# NEW_PDB.net
KiCad netlist of a schematic drawn in Altium Designer
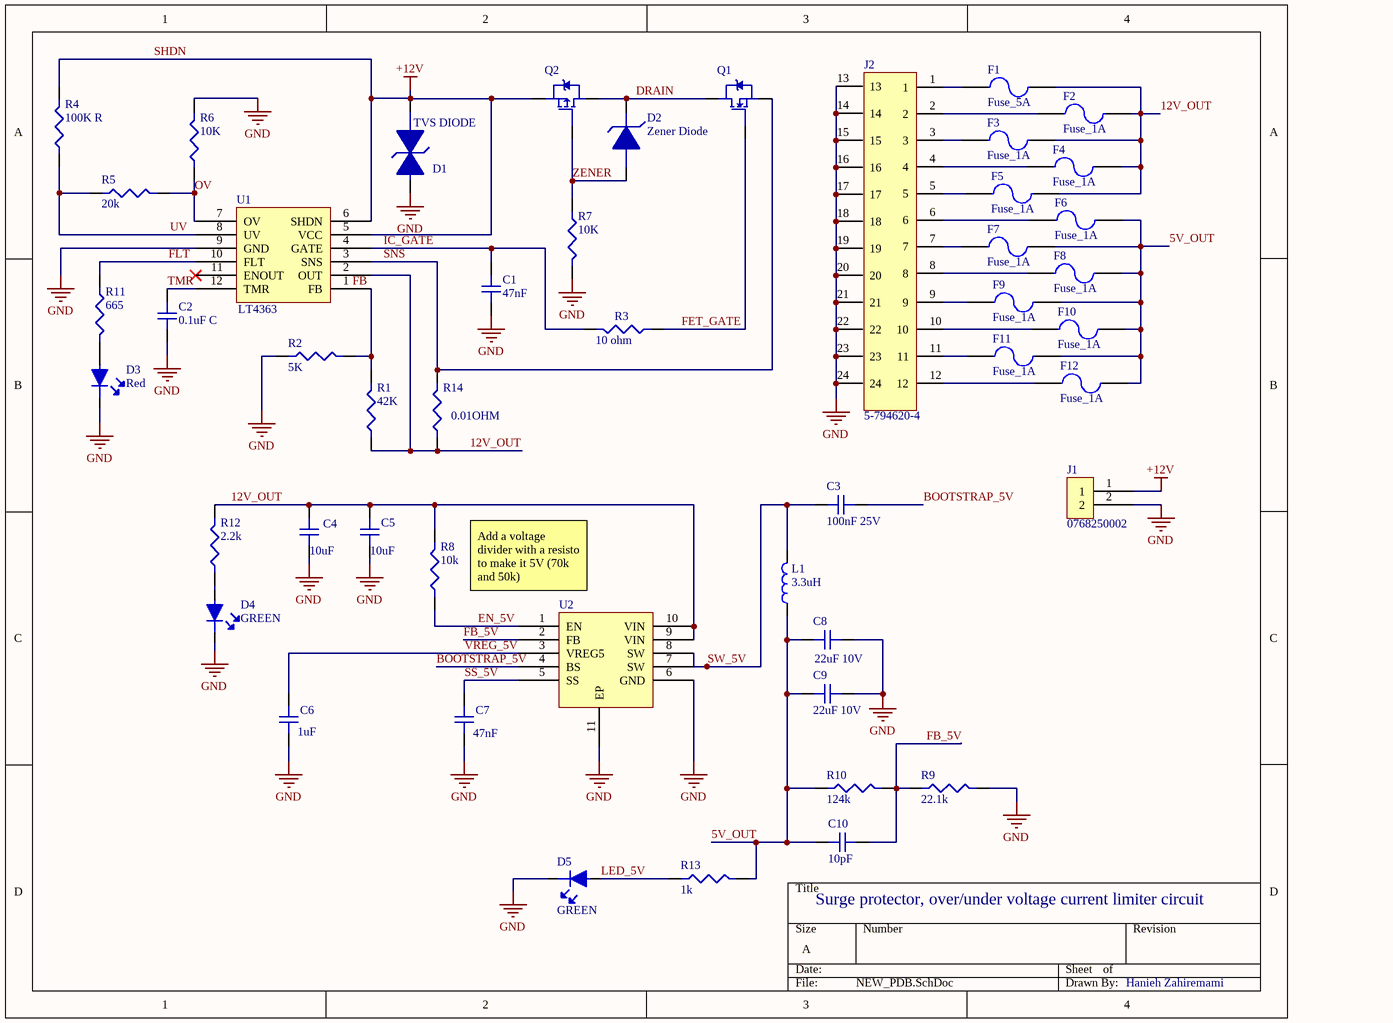
[diagram p0: NEW_PDB.SchDoc]

(export (version "E")
  (design (tool "Eeschema 10.0.6"))
  (components
    (comp (ref "C1")
      (value "47nF")
      (footprint "CAPC1613X09N")
      (description "CAP CER 0.047UF 50V X7R 0603")
      (fields
        (field (name "MANUFACTURER") "Murata")
        (field (name "MANUFACTURER PART NUMBER") "GCM188R71H473KA55D")
      )
      (libsource (lib "PDB_components") (part "GCM188R71H473KA55D"))
    )
    (comp (ref "C2")
      (value "0.1uF C")
      (footprint "CAPC1613X09N")
      (description "Cap Ceramic 0.1uF 25V X5R 10% SMD 0402 85C Paper T/R")
      (fields
        (field (name "MANUFACTURER") "Samsung")
        (field (name "MANUFACTURER PART NUMBER") "CL05A104KA5NNNC")
      )
      (libsource (lib "PDB_components") (part "CL05A104KA5NNNC"))
    )
    (comp (ref "C3")
      (value "100nF 25V")
      (footprint "CAPC1613X09N")
      (description "CAP CER 0.047UF 50V X7R 0603")
      (fields
        (field (name "MANUFACTURER") "Murata")
        (field (name "MANUFACTURER PART NUMBER") "GCM188R71H473KA55D")
      )
      (libsource (lib "PDB_components") (part "GCM188R71H473KA55D"))
    )
    (comp (ref "C4")
      (value "10uF")
      (footprint "CAPC1613X09N")
      (description "CAP CER 0.047UF 50V X7R 0603")
      (fields
        (field (name "MANUFACTURER") "Murata")
        (field (name "MANUFACTURER PART NUMBER") "GCM188R71H473KA55D")
      )
      (libsource (lib "PDB_components") (part "GCM188R71H473KA55D"))
    )
    (comp (ref "C5")
      (value "10uF")
      (footprint "CAPC1613X09N")
      (description "CAP CER 0.047UF 50V X7R 0603")
      (fields
        (field (name "MANUFACTURER") "Murata")
        (field (name "MANUFACTURER PART NUMBER") "GCM188R71H473KA55D")
      )
      (libsource (lib "PDB_components") (part "GCM188R71H473KA55D"))
    )
    (comp (ref "C6")
      (value "1uF")
      (footprint "CAPC1613X09N")
      (description "CAP CER 0.047UF 50V X7R 0603")
      (fields
        (field (name "MANUFACTURER") "Murata")
        (field (name "MANUFACTURER PART NUMBER") "GCM188R71H473KA55D")
      )
      (libsource (lib "PDB_components") (part "GCM188R71H473KA55D"))
    )
    (comp (ref "C7")
      (value "47nF")
      (footprint "CAPC1613X09N")
      (description "CAP CER 0.047UF 50V X7R 0603")
      (fields
        (field (name "MANUFACTURER") "Murata")
        (field (name "MANUFACTURER PART NUMBER") "GCM188R71H473KA55D")
      )
      (libsource (lib "PDB_components") (part "GCM188R71H473KA55D"))
    )
    (comp (ref "C8")
      (value "22uF 10V")
      (footprint "CAPC1613X09N")
      (description "CAP CER 0.047UF 50V X7R 0603")
      (fields
        (field (name "MANUFACTURER") "Murata")
        (field (name "MANUFACTURER PART NUMBER") "GCM188R71H473KA55D")
      )
      (libsource (lib "PDB_components") (part "GCM188R71H473KA55D"))
    )
    (comp (ref "C9")
      (value "22uF 10V")
      (footprint "CAPC1613X09N")
      (description "CAP CER 0.047UF 50V X7R 0603")
      (fields
        (field (name "MANUFACTURER") "Murata")
        (field (name "MANUFACTURER PART NUMBER") "GCM188R71H473KA55D")
      )
      (libsource (lib "PDB_components") (part "GCM188R71H473KA55D"))
    )
    (comp (ref "C10")
      (value "10pF")
      (footprint "CAPC1613X09N")
      (description "CAP CER 0.047UF 50V X7R 0603")
      (fields
        (field (name "MANUFACTURER") "Murata")
        (field (name "MANUFACTURER PART NUMBER") "GCM188R71H473KA55D")
      )
      (libsource (lib "PDB_components") (part "GCM188R71H473KA55D"))
    )
    (comp (ref "D1")
      (value "TVS DIODE")
      (footprint "DIODE_TVS")
      (description "TVS DIODE 58VWM 93.6VC SMA")
      (fields (field (name "MANUFACTURER") "Diodes") (field (name "MANUFACTURER PART NUMBER") "SMAJ58A-13-F"))
      (libsource (lib "PDB_components") (part "SMAJ58A-13-F"))
    )
    (comp (ref "D2")
      (value "Zener Diode")
      (footprint "DIOM3716X14N")
      (description "DIODE GEN PURP 100V 150MA SOD123")
      (fields (field (name "MANUFACTURER") "MCC") (field (name "MANUFACTURER PART NUMBER") "1N4148W-TP"))
      (libsource (lib "PDB_components") (part "1N4148W-TP"))
    )
    (comp (ref "D3")
      (value "Red")
      (footprint "LED2")
      (description "LED RED CLEAR 0603 SMD")
      (fields
        (field (name "MANUFACTURER") "Wurth Electronics")
        (field (name "MANUFACTURER PART NUMBER") "150060VS75000")
      )
      (libsource (lib "PDB_components") (part "150060VS75000"))
    )
    (comp (ref "D4")
      (value "GREEN")
      (footprint "LED2")
      (description "LED GREEN CLEAR 0603 SMD")
      (fields
        (field (name "MANUFACTURER") "Wurth Electronics")
        (field (name "MANUFACTURER PART NUMBER") "150060VS75000")
      )
      (libsource (lib "PDB_components") (part "150060VS75000"))
    )
    (comp (ref "D5")
      (value "GREEN")
      (footprint "LED2")
      (description "LED GREEN CLEAR 0603 SMD")
      (fields
        (field (name "MANUFACTURER") "Wurth Electronics")
        (field (name "MANUFACTURER PART NUMBER") "150060VS75000")
      )
      (libsource (lib "PDB_components") (part "150060VS75000"))
    )
    (comp (ref "F1")
      (value "Fuse_5A")
      (footprint "PDB_Components:FUSE")
      (description "0466005.NR FUSE BOARD MNT 5A 32VAC/VDC 1206")
      (fields (field (name "PUBLISHER") "Altium Limited"))
      (libsource (lib "Miscellaneous Devices") (part "Fuse 2"))
    )
    (comp (ref "F2")
      (value "Fuse_1A")
      (footprint "FUSE")
      (description "0466001.NR FUSE BOARD MNT 1A 63VAC/VDC 1206")
      (fields (field (name "PUBLISHER") "Altium Limited"))
      (libsource (lib "Miscellaneous Devices") (part "Fuse 2"))
    )
    (comp (ref "F3")
      (value "Fuse_1A")
      (footprint "FUSE")
      (description "0466001.NR FUSE BOARD MNT 1A 63VAC/VDC 1206")
      (fields (field (name "PUBLISHER") "Altium Limited"))
      (libsource (lib "Miscellaneous Devices") (part "Fuse 2"))
    )
    (comp (ref "F4")
      (value "Fuse_1A")
      (footprint "FUSE")
      (description "0466001.NR FUSE BOARD MNT 1A 63VAC/VDC 1206")
      (fields (field (name "PUBLISHER") "Altium Limited"))
      (libsource (lib "Miscellaneous Devices") (part "Fuse 2"))
    )
    (comp (ref "F5")
      (value "Fuse_1A")
      (footprint "FUSE")
      (description "0466001.NR FUSE BOARD MNT 1A 63VAC/VDC 1206")
      (fields (field (name "PUBLISHER") "Altium Limited"))
      (libsource (lib "Miscellaneous Devices") (part "Fuse 2"))
    )
    (comp (ref "F6")
      (value "Fuse_1A")
      (footprint "FUSE")
      (description "0466001.NR FUSE BOARD MNT 1A 63VAC/VDC 1206")
      (fields (field (name "PUBLISHER") "Altium Limited"))
      (libsource (lib "Miscellaneous Devices") (part "Fuse 2"))
    )
    (comp (ref "F7")
      (value "Fuse_1A")
      (footprint "FUSE")
      (description "0466001.NR FUSE BOARD MNT 1A 63VAC/VDC 1206")
      (fields (field (name "PUBLISHER") "Altium Limited"))
      (libsource (lib "Miscellaneous Devices") (part "Fuse 2"))
    )
    (comp (ref "F8")
      (value "Fuse_1A")
      (footprint "FUSE")
      (description "0466001.NR FUSE BOARD MNT 1A 63VAC/VDC 1206")
      (fields (field (name "PUBLISHER") "Altium Limited"))
      (libsource (lib "Miscellaneous Devices") (part "Fuse 2"))
    )
    (comp (ref "F9")
      (value "Fuse_1A")
      (footprint "FUSE")
      (description "0466001.NR FUSE BOARD MNT 1A 63VAC/VDC 1206")
      (fields (field (name "PUBLISHER") "Altium Limited"))
      (libsource (lib "Miscellaneous Devices") (part "Fuse 2"))
    )
    (comp (ref "F10")
      (value "Fuse_1A")
      (footprint "FUSE")
      (description "0466001.NR FUSE BOARD MNT 1A 63VAC/VDC 1206")
      (fields (field (name "PUBLISHER") "Altium Limited"))
      (libsource (lib "Miscellaneous Devices") (part "Fuse 2"))
    )
    (comp (ref "F11")
      (value "Fuse_1A")
      (footprint "FUSE")
      (description "0466001.NR FUSE BOARD MNT 1A 63VAC/VDC 1206")
      (fields (field (name "PUBLISHER") "Altium Limited"))
      (libsource (lib "Miscellaneous Devices") (part "Fuse 2"))
    )
    (comp (ref "F12")
      (value "Fuse_1A")
      (footprint "FUSE")
      (description "0466001.NR FUSE BOARD MNT 1A 63VAC/VDC 1206")
      (fields (field (name "PUBLISHER") "Altium Limited"))
      (libsource (lib "Miscellaneous Devices") (part "Fuse 2"))
    )
    (comp (ref "J1")
      (value "0768250002")
      (footprint "MOLEX_2PIN_MEGAFIT")
      (description "CONN_2Position_MEGAFIT Molex Through Hole, Right Angle Tin")
      (fields (field (name "MANUFACTURER") "Molex"))
      (libsource (lib "PDB_components") (part "0768250002"))
    )
    (comp (ref "J2")
      (value "5-794620-4")
      (footprint "PDB_OUT")
      (description "CONN HEADER R/A 24POS 3MM")
      (libsource (lib "PDB_components") (part "5-794620-4"))
    )
    (comp (ref "L1")
      (value "3.3uH")
      (footprint "IND-6mm")
      (description "IND 3.3µH 6.5A 25.2 mOhm Max Nonstandard")
      (fields
        (field (name "MANUFACTURER") "Murata")
        (field (name "MANUFACTURER PART NUMBER") "1264EY-3R3N=P3")
      )
      (libsource (lib "PDB_components") (part "1264EY-3R3N=P3"))
    )
    (comp (ref "Q1")
      (value "IRLR2908TRLPBF")
      (footprint "DPAK")
      (description "MOSFET N-CH 80V 30A DPAK")
      (fields (field (name "MANUFACTURER") "International Rectifier"))
      (libsource (lib "PDB_components") (part "IRLR2908TRLPBF"))
    )
    (comp (ref "Q2")
      (value "STD35P6LLF6")
      (footprint "DPAK")
      (description "POWER MOSFET")
      (fields (field (name "MANUFACTURER") "STMicroelectronics"))
      (libsource (lib "PDB_components") (part "STD35P6LLF6"))
    )
    (comp (ref "R1")
      (value "42K")
      (footprint "R0805")
      (description "Res Thin Film 0805 100K Ohm 0.1% 0.125W(1/8W) ±25ppm/C Molded SMD Automotive Punched T/R")
      (fields
        (field (name "MANUFACTURER") "Panasonic")
        (field (name "MANUFACTURER PART NUMBER") "ERA-6AEB104V")
      )
      (libsource (lib "") (part "ERA-6AEB104V_1"))
    )
    (comp (ref "R2")
      (value "5K")
      (footprint "PDB_Components:R0805")
      (description "Thin Film Resistors - SMD 200mW 5Kohm 0.1% 25ppm")
      (fields
        (field (name "MANUFACTURER") "Vishay Dale Thin Film")
        (field (name "MANUFACTURER PART NUMBER") "PNM0805E5001BST5")
      )
      (libsource (lib "PDB_components") (part "PNM0805E5001BST5_1"))
    )
    (comp (ref "R3")
      (value "10 ohm")
      (footprint "R0805")
      (description "RES SMD 10 OHM 1% 1/3W 0805")
      (fields
        (field (name "MANUFACTURER") "Susumu")
        (field (name "MANUFACTURER PART NUMBER") "RL1220S-100-F")
      )
      (libsource (lib "PDB_components") (part "RL1220S-100-F"))
    )
    (comp (ref "R4")
      (value "100K R")
      (footprint "R0805")
      (description "RES 220K OHM 1/8W 1% 0805 SMD")
      (fields (field (name "MANUFACTURER") "Rohm") (field (name "MANUFACTURER PART NUMBER") "KTR10EZPF2203"))
      (libsource (lib "PDB_components") (part "KTR10EZPF2203"))
    )
    (comp (ref "R5")
      (value "20k")
      (footprint "R0805")
      (description "Res Thin Film 0805 10K Ohm 0.5% 0.1W(1/10W) ±25ppm/C Molded SMD Paper T/R")
      (fields
        (field (name "MANUFACTURER") "Stackpole Electronics")
        (field (name "MANUFACTURER PART NUMBER") "RNCF0805DTE10K0")
      )
      (libsource (lib "PDB_components") (part "RNCF0805DTE10K0"))
    )
    (comp (ref "R6")
      (value "10K")
      (footprint "R0805")
      (description "Res Thin Film 0805 10K Ohm 0.5% 0.1W(1/10W) ±25ppm/C Molded SMD Paper T/R")
      (fields
        (field (name "MANUFACTURER") "Stackpole Electronics")
        (field (name "MANUFACTURER PART NUMBER") "RNCF0805DTE10K0")
      )
      (libsource (lib "PDB_components") (part "RNCF0805DTE10K0"))
    )
    (comp (ref "R7")
      (value "10K")
      (footprint "R0805")
      (description "Res Thin Film 0805 10K Ohm 0.5% 0.1W(1/10W) ±25ppm/C Molded SMD Paper T/R")
      (fields
        (field (name "MANUFACTURER") "Stackpole Electronics")
        (field (name "MANUFACTURER PART NUMBER") "RNCF0805DTE10K0")
      )
      (libsource (lib "PDB_components") (part "RNCF0805DTE10K0"))
    )
    (comp (ref "R8")
      (value "10k")
      (footprint "R0805")
      (description "Res Thin Film 0805 1K Ohm 0.1% 0.125W(1/8W) ±25ppm/C Molded SMD Automotive Punched T/R")
      (fields
        (field (name "MANUFACTURER") "Panasonic")
        (field (name "MANUFACTURER PART NUMBER") "ERA-6AEB104V")
      )
      (libsource (lib "") (part "ERA-6AEB104V_1"))
    )
    (comp (ref "R9")
      (value "22.1k")
      (footprint "R0805")
      (description "Res Thin Film 0805 22.1K Ohm 0.1% 0.125W(1/8W) ±25ppm/C Molded SMD Automotive Punched T/R")
      (fields
        (field (name "MANUFACTURER") "Panasonic")
        (field (name "MANUFACTURER PART NUMBER") "ERA-6AEB104V")
      )
      (libsource (lib "PDB_components") (part "ERA-6AEB104V"))
    )
    (comp (ref "R10")
      (value "124k")
      (footprint "R0805")
      (description "Res Thin Film 0805 124K Ohm 0.1% 0.125W(1/8W) ±25ppm/C Molded SMD Automotive Punched T/R")
      (fields
        (field (name "MANUFACTURER") "Panasonic")
        (field (name "MANUFACTURER PART NUMBER") "ERA-6AEB104V")
      )
      (libsource (lib "PDB_components") (part "ERA-6AEB104V"))
    )
    (comp (ref "R11")
      (value "665")
      (footprint "R0805")
      (description "Res Thin Film 0805 22.1K Ohm 0.1% 0.125W(1/8W) ±25ppm/C Molded SMD Automotive Punched T/R")
      (fields
        (field (name "MANUFACTURER") "Panasonic")
        (field (name "MANUFACTURER PART NUMBER") "ERA-6AEB104V")
      )
      (libsource (lib "PDB_components") (part "ERA-6AEB104V"))
    )
    (comp (ref "R12")
      (value "2.2k")
      (footprint "R0805")
      (description "Res Thin Film 0805 22.1K Ohm 0.1% 0.125W(1/8W) ±25ppm/C Molded SMD Automotive Punched T/R")
      (fields
        (field (name "MANUFACTURER") "Panasonic")
        (field (name "MANUFACTURER PART NUMBER") "ERA-6AEB104V")
      )
      (libsource (lib "PDB_components") (part "ERA-6AEB104V"))
    )
    (comp (ref "R13")
      (value "1k")
      (footprint "R0805")
      (description "Res Thin Film 0805 22.1K Ohm 0.1% 0.125W(1/8W) ±25ppm/C Molded SMD Automotive Punched T/R")
      (fields
        (field (name "MANUFACTURER") "Panasonic")
        (field (name "MANUFACTURER PART NUMBER") "ERA-6AEB104V")
      )
      (libsource (lib "PDB_components") (part "ERA-6AEB104V"))
    )
    (comp (ref "R14")
      (value "0.01OHM")
      (footprint "R2512")
      (description "RES SMD 0.01 OHM 1% 2W 2512")
      (fields
        (field (name "MANUFACTURER") "Yageo")
        (field (name "MANUFACTURER PART NUMBER") "PE2512FKE7W0R01L")
      )
      (libsource (lib "PDB_components") (part "PE2512FKE7W0R01L"))
    )
    (comp (ref "U1")
      (value "LT4363")
      (footprint "TSOP65P490X110-12N")
      (description "IC SURGE STOPPER HV 12-MSOP")
      (fields
        (field (name "MANUFACTURER") "Analog Devices / Linear Technology")
        (field (name "MANUFACTURER PART NUMBER") "LT4363CMS-2#PBF")
      )
      (libsource (lib "PDB_components") (part "LT4363CMS-2#PBF"))
    )
    (comp (ref "U2")
      (value "AP65550FN-7")
      (footprint "DFN-10")
      (description "IC BUCK SYNC 5A, 18V VIN MAX 650kHz COT Step-Down Conv")
      (fields (field (name "MANUFACTURER") "Diodes"))
      (libsource (lib "PDB_components") (part "AP65550FN-7"))
    )
  )
  (nets
    (net (code "1") (name "+12V") (class "Default")
      (node (ref "D1") (pin "2") (pinfunction "2_2") (pintype "passive"))
      (node (ref "J1") (pin "1") (pinfunction "1_1") (pintype "passive"))
      (node (ref "Q2") (pin "3") (pinfunction "3_3") (pintype "passive"))
      (node (ref "R4") (pin "2") (pinfunction "2_2") (pintype "passive"))
      (node (ref "U1") (pin "5") (pinfunction "VCC_5") (pintype "passive"))
      (node (ref "U1") (pin "6") (pinfunction "SHDN_6") (pintype "passive"))
    )
    (net (code "2") (name "/5V_OUT") (class "Default")
      (node (ref "C10") (pin "2") (pinfunction "2_2") (pintype "passive"))
      (node (ref "C8") (pin "2") (pinfunction "2_2") (pintype "passive"))
      (node (ref "C9") (pin "2") (pinfunction "2_2") (pintype "passive"))
      (node (ref "F10") (pin "2") (pinfunction "2_2") (pintype "passive"))
      (node (ref "F11") (pin "2") (pinfunction "2_2") (pintype "passive"))
      (node (ref "F12") (pin "2") (pinfunction "2_2") (pintype "passive"))
      (node (ref "F6") (pin "2") (pinfunction "2_2") (pintype "passive"))
      (node (ref "F7") (pin "2") (pinfunction "2_2") (pintype "passive"))
      (node (ref "F8") (pin "2") (pinfunction "2_2") (pintype "passive"))
      (node (ref "F9") (pin "2") (pinfunction "2_2") (pintype "passive"))
      (node (ref "L1") (pin "1") (pinfunction "1_1") (pintype "passive"))
      (node (ref "R10") (pin "2") (pinfunction "2_2") (pintype "passive"))
      (node (ref "R13") (pin "1") (pinfunction "1_1") (pintype "passive"))
    )
    (net (code "3") (name "/12V_OUT") (class "Default")
      (node (ref "C4") (pin "2") (pinfunction "2_2") (pintype "passive"))
      (node (ref "C5") (pin "2") (pinfunction "2_2") (pintype "passive"))
      (node (ref "F1") (pin "2") (pinfunction "2_2") (pintype "passive"))
      (node (ref "F2") (pin "2") (pinfunction "2_2") (pintype "passive"))
      (node (ref "F3") (pin "2") (pinfunction "2_2") (pintype "passive"))
      (node (ref "F4") (pin "2") (pinfunction "2_2") (pintype "passive"))
      (node (ref "F5") (pin "2") (pinfunction "2_2") (pintype "passive"))
      (node (ref "R1") (pin "1") (pinfunction "1_1") (pintype "passive"))
      (node (ref "R12") (pin "1") (pinfunction "1_1") (pintype "passive"))
      (node (ref "R14") (pin "1") (pinfunction "1_1") (pintype "passive"))
      (node (ref "R8") (pin "2") (pinfunction "2_2") (pintype "passive"))
      (node (ref "U1") (pin "2") (pinfunction "OUT_2") (pintype "passive"))
      (node (ref "U2") (pin "10") (pinfunction "VIN_10") (pintype "passive"))
      (node (ref "U2") (pin "9") (pinfunction "VIN_9") (pintype "passive"))
    )
    (net (code "4") (name "/BOOTSTRAP_5V") (class "Default")
      (node (ref "C3") (pin "1") (pinfunction "1_1") (pintype "passive"))
      (node (ref "U2") (pin "4") (pinfunction "BS_4") (pintype "passive"))
    )
    (net (code "5") (name "/DRAIN") (class "Default")
      (node (ref "D2") (pin "1") (pinfunction "1_1") (pintype "passive"))
      (node (ref "Q1") (pin "4") (pinfunction "4_4") (pintype "passive"))
      (node (ref "Q2") (pin "4") (pinfunction "4_4") (pintype "passive"))
    )
    (net (code "6") (name "/EN_5V") (class "Default")
      (node (ref "R8") (pin "1") (pinfunction "1_1") (pintype "passive"))
      (node (ref "U2") (pin "1") (pinfunction "EN_1") (pintype "passive"))
    )
    (net (code "8") (name "/FB_5V") (class "Default")
      (node (ref "C10") (pin "1") (pinfunction "1_1") (pintype "passive"))
      (node (ref "R10") (pin "1") (pinfunction "1_1") (pintype "passive"))
      (node (ref "R9") (pin "2") (pinfunction "2_2") (pintype "passive"))
      (node (ref "U2") (pin "2") (pinfunction "FB_2") (pintype "passive"))
    )
    (net (code "9") (name "/FET_GATE") (class "Default")
      (node (ref "Q1") (pin "1") (pinfunction "1_1") (pintype "passive"))
      (node (ref "R3") (pin "1") (pinfunction "1_1") (pintype "passive"))
    )
    (net (code "10") (name "/FLT") (class "Default")
      (node (ref "R11") (pin "2") (pinfunction "2_2") (pintype "passive"))
      (node (ref "U1") (pin "10") (pinfunction "FLT_10") (pintype "passive"))
    )
    (net (code "11") (name "/IC_GATE") (class "Default")
      (node (ref "C1") (pin "2") (pinfunction "2_2") (pintype "passive"))
      (node (ref "R3") (pin "2") (pinfunction "2_2") (pintype "passive"))
      (node (ref "U1") (pin "4") (pinfunction "GATE_4") (pintype "passive"))
    )
    (net (code "12") (name "/LED_5V") (class "Default")
      (node (ref "D5") (pin "1") (pinfunction "1_1") (pintype "passive"))
      (node (ref "R13") (pin "2") (pinfunction "2_2") (pintype "passive"))
    )
    (net (code "13") (name "/OV") (class "Default")
      (node (ref "R5") (pin "2") (pinfunction "2_2") (pintype "passive"))
      (node (ref "R6") (pin "1") (pinfunction "1_1") (pintype "passive"))
      (node (ref "U1") (pin "7") (pinfunction "OV_7") (pintype "passive"))
    )
    (net (code "14") (name "/SNS") (class "Default")
      (node (ref "Q1") (pin "3") (pinfunction "3_3") (pintype "passive"))
      (node (ref "R14") (pin "2") (pinfunction "2_2") (pintype "passive"))
      (node (ref "U1") (pin "3") (pinfunction "SNS_3") (pintype "passive"))
    )
    (net (code "15") (name "/SS_5V") (class "Default")
      (node (ref "C7") (pin "2") (pinfunction "2_2") (pintype "passive"))
      (node (ref "U2") (pin "5") (pinfunction "SS_5") (pintype "passive"))
    )
    (net (code "16") (name "/SW_5V") (class "Default")
      (node (ref "C3") (pin "2") (pinfunction "2_2") (pintype "passive"))
      (node (ref "L1") (pin "2") (pinfunction "2_2") (pintype "passive"))
      (node (ref "U2") (pin "7") (pinfunction "SW_7") (pintype "passive"))
      (node (ref "U2") (pin "8") (pinfunction "SW_8") (pintype "passive"))
    )
    (net (code "17") (name "/TMR") (class "Default")
      (node (ref "C2") (pin "2") (pinfunction "2_2") (pintype "passive"))
      (node (ref "U1") (pin "12") (pinfunction "TMR_12") (pintype "passive"))
    )
    (net (code "18") (name "/UV") (class "Default")
      (node (ref "R4") (pin "1") (pinfunction "1_1") (pintype "passive"))
      (node (ref "R5") (pin "1") (pinfunction "1_1") (pintype "passive"))
      (node (ref "U1") (pin "8") (pinfunction "UV_8") (pintype "passive"))
    )
    (net (code "19") (name "/VREG_5V") (class "Default")
      (node (ref "C6") (pin "2") (pinfunction "2_2") (pintype "passive"))
      (node (ref "U2") (pin "3") (pinfunction "VREG5_3") (pintype "passive"))
    )
    (net (code "20") (name "/ZENER") (class "Default")
      (node (ref "D2") (pin "2") (pinfunction "2_2") (pintype "passive"))
      (node (ref "Q2") (pin "1") (pinfunction "1_1") (pintype "passive"))
      (node (ref "R7") (pin "1") (pinfunction "1_1") (pintype "passive"))
    )
    (net (code "21") (name "GND") (class "Default")
      (node (ref "C1") (pin "1") (pinfunction "1_1") (pintype "passive"))
      (node (ref "C2") (pin "1") (pinfunction "1_1") (pintype "passive"))
      (node (ref "C4") (pin "1") (pinfunction "1_1") (pintype "passive"))
      (node (ref "C5") (pin "1") (pinfunction "1_1") (pintype "passive"))
      (node (ref "C6") (pin "1") (pinfunction "1_1") (pintype "passive"))
      (node (ref "C7") (pin "1") (pinfunction "1_1") (pintype "passive"))
      (node (ref "C8") (pin "1") (pinfunction "1_1") (pintype "passive"))
      (node (ref "C9") (pin "1") (pinfunction "1_1") (pintype "passive"))
      (node (ref "D1") (pin "1") (pinfunction "1_1") (pintype "passive"))
      (node (ref "D3") (pin "2") (pinfunction "2_2") (pintype "passive"))
      (node (ref "D4") (pin "2") (pinfunction "2_2") (pintype "passive"))
      (node (ref "D5") (pin "2") (pinfunction "2_2") (pintype "passive"))
      (node (ref "J1") (pin "2") (pinfunction "2_2") (pintype "passive"))
      (node (ref "J2") (pin "13") (pinfunction "13_13") (pintype "passive"))
      (node (ref "J2") (pin "14") (pinfunction "14_14") (pintype "passive"))
      (node (ref "J2") (pin "15") (pinfunction "15_15") (pintype "passive"))
      (node (ref "J2") (pin "16") (pinfunction "16_16") (pintype "passive"))
      (node (ref "J2") (pin "17") (pinfunction "17_17") (pintype "passive"))
      (node (ref "J2") (pin "18") (pinfunction "18_18") (pintype "passive"))
      (node (ref "J2") (pin "19") (pinfunction "19_19") (pintype "passive"))
      (node (ref "J2") (pin "20") (pinfunction "20_20") (pintype "passive"))
      (node (ref "J2") (pin "21") (pinfunction "21_21") (pintype "passive"))
      (node (ref "J2") (pin "22") (pinfunction "22_22") (pintype "passive"))
      (node (ref "J2") (pin "23") (pinfunction "23_23") (pintype "passive"))
      (node (ref "J2") (pin "24") (pinfunction "24_24") (pintype "passive"))
      (node (ref "R2") (pin "1") (pinfunction "1_1") (pintype "passive"))
      (node (ref "R6") (pin "2") (pinfunction "2_2") (pintype "passive"))
      (node (ref "R7") (pin "2") (pinfunction "2_2") (pintype "passive"))
      (node (ref "R9") (pin "1") (pinfunction "1_1") (pintype "passive"))
      (node (ref "U1") (pin "9") (pinfunction "GND_9") (pintype "passive"))
      (node (ref "U2") (pin "11") (pinfunction "EP_11") (pintype "passive"))
      (node (ref "U2") (pin "6") (pinfunction "GND_6") (pintype "passive"))
    )
    (net (code "22") (name "Net-(D3-Pad1)") (class "Default")
      (node (ref "D3") (pin "1") (pinfunction "1_1") (pintype "passive"))
      (node (ref "R11") (pin "1") (pinfunction "1_1") (pintype "passive"))
    )
    (net (code "23") (name "Net-(D4-Pad1)") (class "Default")
      (node (ref "D4") (pin "1") (pinfunction "1_1") (pintype "passive"))
      (node (ref "R12") (pin "2") (pinfunction "2_2") (pintype "passive"))
    )
    (net (code "24") (name "Net-(F1-Pad1)") (class "Default")
      (node (ref "F1") (pin "1") (pinfunction "1_1") (pintype "passive"))
      (node (ref "J2") (pin "1") (pinfunction "1_1") (pintype "passive"))
    )
    (net (code "25") (name "Net-(F2-Pad1)") (class "Default")
      (node (ref "F2") (pin "1") (pinfunction "1_1") (pintype "passive"))
      (node (ref "J2") (pin "2") (pinfunction "2_2") (pintype "passive"))
    )
    (net (code "26") (name "Net-(F3-Pad1)") (class "Default")
      (node (ref "F3") (pin "1") (pinfunction "1_1") (pintype "passive"))
      (node (ref "J2") (pin "3") (pinfunction "3_3") (pintype "passive"))
    )
    (net (code "27") (name "Net-(F4-Pad1)") (class "Default")
      (node (ref "F4") (pin "1") (pinfunction "1_1") (pintype "passive"))
      (node (ref "J2") (pin "4") (pinfunction "4_4") (pintype "passive"))
    )
    (net (code "28") (name "Net-(F5-Pad1)") (class "Default")
      (node (ref "F5") (pin "1") (pinfunction "1_1") (pintype "passive"))
      (node (ref "J2") (pin "5") (pinfunction "5_5") (pintype "passive"))
    )
    (net (code "29") (name "Net-(F6-Pad1)") (class "Default")
      (node (ref "F6") (pin "1") (pinfunction "1_1") (pintype "passive"))
      (node (ref "J2") (pin "6") (pinfunction "6_6") (pintype "passive"))
    )
    (net (code "30") (name "Net-(F7-Pad1)") (class "Default")
      (node (ref "F7") (pin "1") (pinfunction "1_1") (pintype "passive"))
      (node (ref "J2") (pin "7") (pinfunction "7_7") (pintype "passive"))
    )
    (net (code "31") (name "Net-(F8-Pad1)") (class "Default")
      (node (ref "F8") (pin "1") (pinfunction "1_1") (pintype "passive"))
      (node (ref "J2") (pin "8") (pinfunction "8_8") (pintype "passive"))
    )
    (net (code "32") (name "Net-(F9-Pad1)") (class "Default")
      (node (ref "F9") (pin "1") (pinfunction "1_1") (pintype "passive"))
      (node (ref "J2") (pin "9") (pinfunction "9_9") (pintype "passive"))
    )
    (net (code "33") (name "Net-(F10-Pad1)") (class "Default")
      (node (ref "F10") (pin "1") (pinfunction "1_1") (pintype "passive"))
      (node (ref "J2") (pin "10") (pinfunction "10_10") (pintype "passive"))
    )
    (net (code "34") (name "Net-(F11-Pad1)") (class "Default")
      (node (ref "F11") (pin "1") (pinfunction "1_1") (pintype "passive"))
      (node (ref "J2") (pin "11") (pinfunction "11_11") (pintype "passive"))
    )
    (net (code "35") (name "Net-(F12-Pad1)") (class "Default")
      (node (ref "F12") (pin "1") (pinfunction "1_1") (pintype "passive"))
      (node (ref "J2") (pin "12") (pinfunction "12_12") (pintype "passive"))
    )
    (net (code "36") (name "Net-(U1-FB)") (class "Default")
      (node (ref "R1") (pin "2") (pinfunction "2_2") (pintype "passive"))
      (node (ref "R2") (pin "2") (pinfunction "2_2") (pintype "passive"))
      (node (ref "U1") (pin "1") (pinfunction "FB_1") (pintype "passive"))
    )
    (net (code "37") (name "unconnected-(U1-ENOUT-Pad11)") (class "Default")
      (node (ref "U1") (pin "11") (pinfunction "ENOUT_11") (pintype "passive+no_connect"))
    )
  )
)
